# circuit2_ver2.net
KiCad netlist of a schematic drawn in Altium Designer
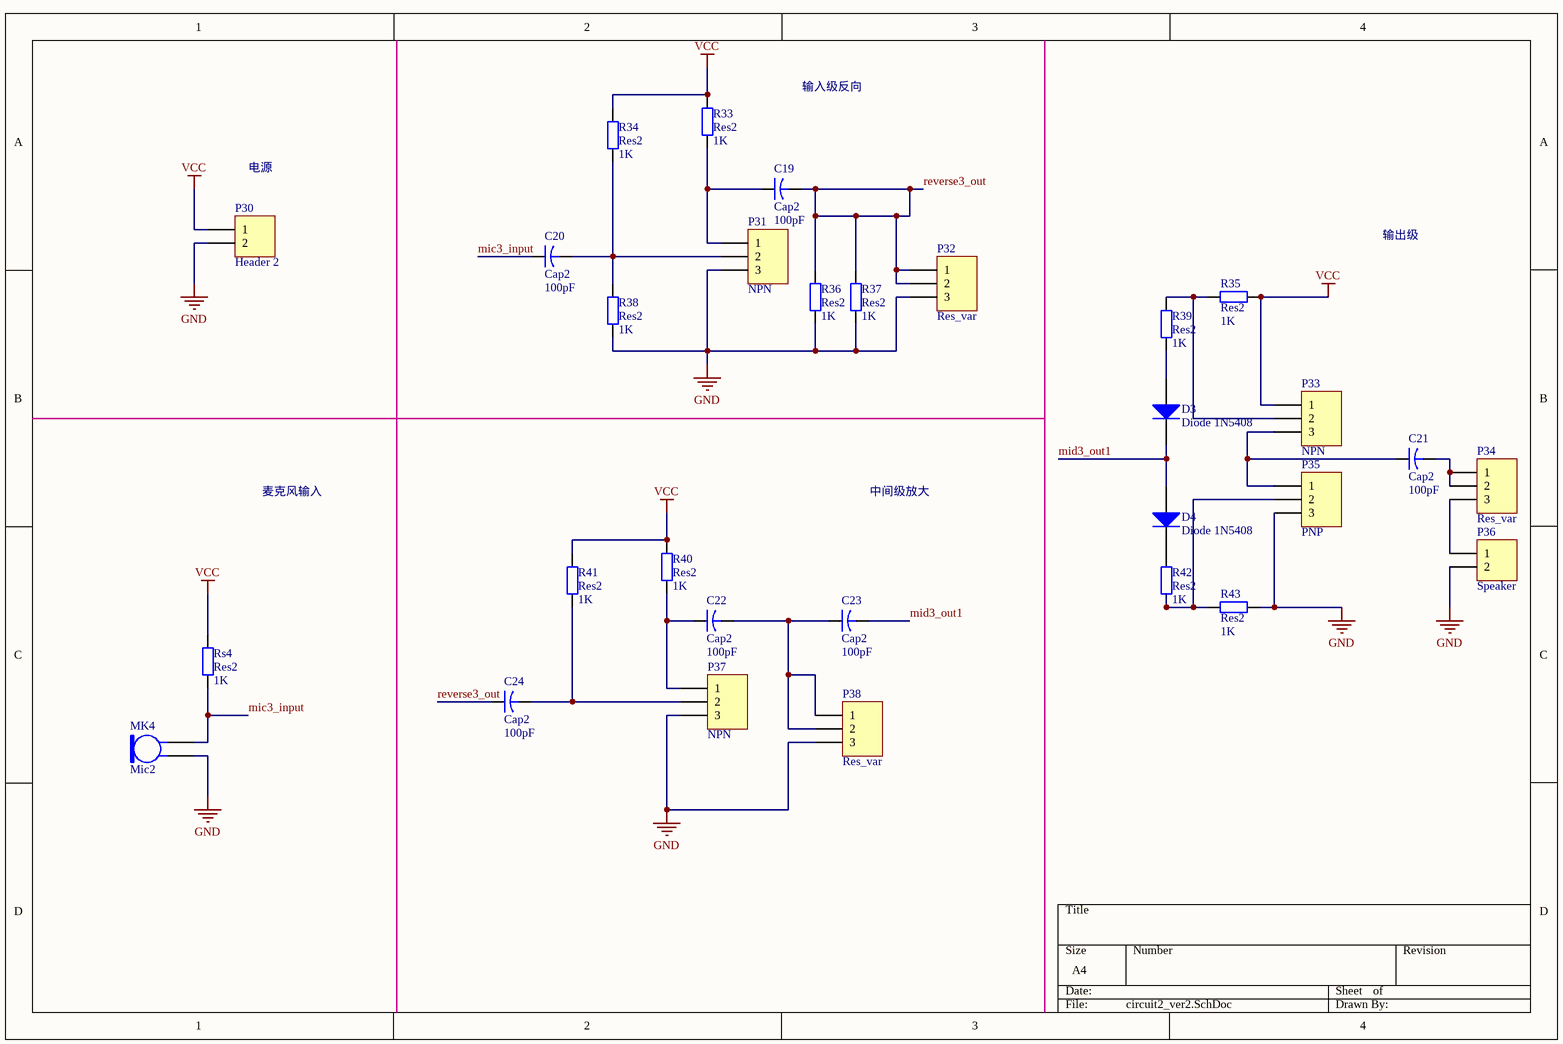
[diagram p0: circuit2_ver2.SchDoc]

(export (version "E")
  (design (tool "Eeschema 10.0.6"))
  (components
    (comp (ref "C19")
      (value "Cap2")
      (footprint "CAPR5-4X5")
      (description "Capacitor")
      (fields (field (name "ALTIUM_VALUE") "100pF") (field (name "PUBLISHER") "Altium Limited"))
      (libsource (lib "Miscellaneous Devices") (part "Cap2"))
    )
    (comp (ref "C20")
      (value "Cap2")
      (footprint "CAPR5-4X5")
      (description "Capacitor")
      (fields (field (name "ALTIUM_VALUE") "100pF") (field (name "PUBLISHER") "Altium Limited"))
      (libsource (lib "Miscellaneous Devices") (part "Cap2"))
    )
    (comp (ref "C21")
      (value "Cap2")
      (footprint "CAPR5-4X5")
      (description "Capacitor")
      (fields (field (name "ALTIUM_VALUE") "100pF") (field (name "PUBLISHER") "Altium Limited"))
      (libsource (lib "Miscellaneous Devices") (part "Cap2"))
    )
    (comp (ref "C22")
      (value "Cap2")
      (footprint "CAPR5-4X5")
      (description "Capacitor")
      (fields (field (name "ALTIUM_VALUE") "100pF") (field (name "PUBLISHER") "Altium Limited"))
      (libsource (lib "Miscellaneous Devices") (part "Cap2"))
    )
    (comp (ref "C23")
      (value "Cap2")
      (footprint "CAPR5-4X5")
      (description "Capacitor")
      (fields (field (name "ALTIUM_VALUE") "100pF") (field (name "PUBLISHER") "Altium Limited"))
      (libsource (lib "Miscellaneous Devices") (part "Cap2"))
    )
    (comp (ref "C24")
      (value "Cap2")
      (footprint "CAPR5-4X5")
      (description "Capacitor")
      (fields (field (name "ALTIUM_VALUE") "100pF") (field (name "PUBLISHER") "Altium Limited"))
      (libsource (lib "Miscellaneous Devices") (part "Cap2"))
    )
    (comp (ref "D3")
      (value "Diode 1N5408")
      (footprint "DO-201AD")
      (description "3 Amp Medium Power Silicon Rectifier Diode")
      (fields (field (name "PUBLISHER") "Altium Limited"))
      (libsource (lib "Miscellaneous Devices") (part "Diode 1N5408"))
    )
    (comp (ref "D4")
      (value "Diode 1N5408")
      (footprint "DO-201AD")
      (description "3 Amp Medium Power Silicon Rectifier Diode")
      (fields (field (name "PUBLISHER") "Altium Limited"))
      (libsource (lib "Miscellaneous Devices") (part "Diode 1N5408"))
    )
    (comp (ref "MK4")
      (value "Mic2")
      (footprint "PIN2")
      (description "Microphone")
      (fields (field (name "PUBLISHER") "Altium Limited"))
      (libsource (lib "Miscellaneous Devices") (part "Mic2"))
    )
    (comp (ref "P30")
      (value "Header 2")
      (footprint "HDR1X2")
      (description "Header, 2-Pin")
      (fields (field (name "PUBLISHER") "Altium Limited"))
      (libsource (lib "Miscellaneous Connectors") (part "Header 2"))
    )
    (comp (ref "P31")
      (value "NPN")
      (footprint "HDR1X3")
      (description "Header, 3-Pin")
      (fields (field (name "PUBLISHER") "Altium Limited"))
      (libsource (lib "Miscellaneous Connectors") (part "Header 3"))
    )
    (comp (ref "P32")
      (value "Res_var")
      (footprint "HDR1X3")
      (description "Header, 3-Pin")
      (fields (field (name "PUBLISHER") "Altium Limited"))
      (libsource (lib "Miscellaneous Connectors") (part "Header 3"))
    )
    (comp (ref "P33")
      (value "NPN")
      (footprint "HDR1X3")
      (description "Header, 3-Pin")
      (fields (field (name "PUBLISHER") "Altium Limited"))
      (libsource (lib "Miscellaneous Connectors") (part "Header 3"))
    )
    (comp (ref "P34")
      (value "Res_var")
      (footprint "HDR1X3")
      (description "Header, 3-Pin")
      (fields (field (name "PUBLISHER") "Altium Limited"))
      (libsource (lib "Miscellaneous Connectors") (part "Header 3"))
    )
    (comp (ref "P35")
      (value "PNP")
      (footprint "HDR1X3")
      (description "Header, 3-Pin")
      (fields (field (name "PUBLISHER") "Altium Limited"))
      (libsource (lib "Miscellaneous Connectors") (part "Header 3"))
    )
    (comp (ref "P36")
      (value "Speaker")
      (footprint "HDR1X2")
      (description "Header, 2-Pin")
      (fields (field (name "PUBLISHER") "Altium Limited"))
      (libsource (lib "Miscellaneous Connectors") (part "Header 2"))
    )
    (comp (ref "P37")
      (value "NPN")
      (footprint "HDR1X3")
      (description "Header, 3-Pin")
      (fields (field (name "PUBLISHER") "Altium Limited"))
      (libsource (lib "Miscellaneous Connectors") (part "Header 3"))
    )
    (comp (ref "P38")
      (value "Res_var")
      (footprint "HDR1X3")
      (description "Header, 3-Pin")
      (fields (field (name "PUBLISHER") "Altium Limited"))
      (libsource (lib "Miscellaneous Connectors") (part "Header 3"))
    )
    (comp (ref "R33")
      (value "Res2")
      (footprint "AXIAL-0.4")
      (description "Resistor")
      (fields (field (name "ALTIUM_VALUE") "1K") (field (name "PUBLISHER") "Altium Limited"))
      (libsource (lib "Miscellaneous Devices") (part "Res2"))
    )
    (comp (ref "R34")
      (value "Res2")
      (footprint "AXIAL-0.4")
      (description "Resistor")
      (fields (field (name "ALTIUM_VALUE") "1K") (field (name "PUBLISHER") "Altium Limited"))
      (libsource (lib "Miscellaneous Devices") (part "Res2"))
    )
    (comp (ref "R35")
      (value "Res2")
      (footprint "AXIAL-0.4")
      (description "Resistor")
      (fields (field (name "ALTIUM_VALUE") "1K") (field (name "PUBLISHER") "Altium Limited"))
      (libsource (lib "") (part "Res2_1"))
    )
    (comp (ref "R36")
      (value "Res2")
      (footprint "AXIAL-0.4")
      (description "Resistor")
      (fields (field (name "ALTIUM_VALUE") "1K") (field (name "PUBLISHER") "Altium Limited"))
      (libsource (lib "Miscellaneous Devices") (part "Res2"))
    )
    (comp (ref "R37")
      (value "Res2")
      (footprint "AXIAL-0.4")
      (description "Resistor")
      (fields (field (name "ALTIUM_VALUE") "1K") (field (name "PUBLISHER") "Altium Limited"))
      (libsource (lib "Miscellaneous Devices") (part "Res2"))
    )
    (comp (ref "R38")
      (value "Res2")
      (footprint "AXIAL-0.4")
      (description "Resistor")
      (fields (field (name "ALTIUM_VALUE") "1K") (field (name "PUBLISHER") "Altium Limited"))
      (libsource (lib "Miscellaneous Devices") (part "Res2"))
    )
    (comp (ref "R39")
      (value "Res2")
      (footprint "AXIAL-0.4")
      (description "Resistor")
      (fields (field (name "ALTIUM_VALUE") "1K") (field (name "PUBLISHER") "Altium Limited"))
      (libsource (lib "Miscellaneous Devices") (part "Res2"))
    )
    (comp (ref "R40")
      (value "Res2")
      (footprint "AXIAL-0.4")
      (description "Resistor")
      (fields (field (name "ALTIUM_VALUE") "1K") (field (name "PUBLISHER") "Altium Limited"))
      (libsource (lib "Miscellaneous Devices") (part "Res2"))
    )
    (comp (ref "R41")
      (value "Res2")
      (footprint "AXIAL-0.4")
      (description "Resistor")
      (fields (field (name "ALTIUM_VALUE") "1K") (field (name "PUBLISHER") "Altium Limited"))
      (libsource (lib "Miscellaneous Devices") (part "Res2"))
    )
    (comp (ref "R42")
      (value "Res2")
      (footprint "AXIAL-0.4")
      (description "Resistor")
      (fields (field (name "ALTIUM_VALUE") "1K") (field (name "PUBLISHER") "Altium Limited"))
      (libsource (lib "Miscellaneous Devices") (part "Res2"))
    )
    (comp (ref "R43")
      (value "Res2")
      (footprint "AXIAL-0.4")
      (description "Resistor")
      (fields (field (name "ALTIUM_VALUE") "1K") (field (name "PUBLISHER") "Altium Limited"))
      (libsource (lib "") (part "Res2_1"))
    )
    (comp (ref "Rs4")
      (value "Res2")
      (footprint "AXIAL-0.4")
      (description "Resistor")
      (fields (field (name "ALTIUM_VALUE") "1K") (field (name "PUBLISHER") "Altium Limited"))
      (libsource (lib "Miscellaneous Devices") (part "Res2"))
    )
  )
  (nets
    (net (code "1") (name "/mic3_input") (class "Default")
      (node (ref "C20") (pin "1") (pinfunction "1_1") (pintype "passive"))
      (node (ref "MK4") (pin "2") (pinfunction "2_2") (pintype "passive"))
      (node (ref "Rs4") (pin "1") (pinfunction "1_1") (pintype "passive"))
    )
    (net (code "2") (name "/mid3_out1") (class "Default")
      (node (ref "C23") (pin "2") (pinfunction "2_2") (pintype "passive"))
      (node (ref "D3") (pin "2") (pinfunction "K_2") (pintype "passive"))
      (node (ref "D4") (pin "1") (pinfunction "A_1") (pintype "passive"))
    )
    (net (code "3") (name "/reverse3_out") (class "Default")
      (node (ref "C19") (pin "2") (pinfunction "2_2") (pintype "passive"))
      (node (ref "C24") (pin "1") (pinfunction "1_1") (pintype "passive"))
      (node (ref "P32") (pin "1") (pinfunction "1_1") (pintype "passive"))
      (node (ref "P32") (pin "2") (pinfunction "2_2") (pintype "passive"))
      (node (ref "R36") (pin "2") (pinfunction "2_2") (pintype "passive"))
      (node (ref "R37") (pin "2") (pinfunction "2_2") (pintype "passive"))
    )
    (net (code "4") (name "GND") (class "Default")
      (node (ref "MK4") (pin "1") (pinfunction "1_1") (pintype "passive"))
      (node (ref "P30") (pin "2") (pinfunction "2_2") (pintype "passive"))
      (node (ref "P31") (pin "3") (pinfunction "3_3") (pintype "passive"))
      (node (ref "P32") (pin "3") (pinfunction "3_3") (pintype "passive"))
      (node (ref "P35") (pin "3") (pinfunction "3_3") (pintype "passive"))
      (node (ref "P36") (pin "2") (pinfunction "2_2") (pintype "passive"))
      (node (ref "P37") (pin "3") (pinfunction "3_3") (pintype "passive"))
      (node (ref "P38") (pin "3") (pinfunction "3_3") (pintype "passive"))
      (node (ref "R36") (pin "1") (pinfunction "1_1") (pintype "passive"))
      (node (ref "R37") (pin "1") (pinfunction "1_1") (pintype "passive"))
      (node (ref "R38") (pin "1") (pinfunction "1_1") (pintype "passive"))
      (node (ref "R43") (pin "1") (pinfunction "1_1") (pintype "passive"))
    )
    (net (code "5") (name "Net-(C19-Pad1)") (class "Default")
      (node (ref "C19") (pin "1") (pinfunction "1_1") (pintype "passive"))
      (node (ref "P31") (pin "1") (pinfunction "1_1") (pintype "passive"))
      (node (ref "R33") (pin "1") (pinfunction "1_1") (pintype "passive"))
    )
    (net (code "6") (name "Net-(C20-Pad2)") (class "Default")
      (node (ref "C20") (pin "2") (pinfunction "2_2") (pintype "passive"))
      (node (ref "P31") (pin "2") (pinfunction "2_2") (pintype "passive"))
      (node (ref "R34") (pin "1") (pinfunction "1_1") (pintype "passive"))
      (node (ref "R38") (pin "2") (pinfunction "2_2") (pintype "passive"))
    )
    (net (code "7") (name "Net-(C21-Pad1)") (class "Default")
      (node (ref "C21") (pin "1") (pinfunction "1_1") (pintype "passive"))
      (node (ref "P33") (pin "3") (pinfunction "3_3") (pintype "passive"))
      (node (ref "P35") (pin "1") (pinfunction "1_1") (pintype "passive"))
    )
    (net (code "8") (name "Net-(C21-Pad2)") (class "Default")
      (node (ref "C21") (pin "2") (pinfunction "2_2") (pintype "passive"))
      (node (ref "P34") (pin "1") (pinfunction "1_1") (pintype "passive"))
      (node (ref "P34") (pin "2") (pinfunction "2_2") (pintype "passive"))
    )
    (net (code "9") (name "Net-(C22-Pad1)") (class "Default")
      (node (ref "C22") (pin "1") (pinfunction "1_1") (pintype "passive"))
      (node (ref "P37") (pin "1") (pinfunction "1_1") (pintype "passive"))
      (node (ref "R40") (pin "1") (pinfunction "1_1") (pintype "passive"))
    )
    (net (code "10") (name "Net-(C22-Pad2)") (class "Default")
      (node (ref "C22") (pin "2") (pinfunction "2_2") (pintype "passive"))
      (node (ref "C23") (pin "1") (pinfunction "1_1") (pintype "passive"))
      (node (ref "P38") (pin "1") (pinfunction "1_1") (pintype "passive"))
      (node (ref "P38") (pin "2") (pinfunction "2_2") (pintype "passive"))
    )
    (net (code "11") (name "Net-(C24-Pad2)") (class "Default")
      (node (ref "C24") (pin "2") (pinfunction "2_2") (pintype "passive"))
      (node (ref "P37") (pin "2") (pinfunction "2_2") (pintype "passive"))
      (node (ref "R41") (pin "1") (pinfunction "1_1") (pintype "passive"))
    )
    (net (code "12") (name "Net-(D3-A)") (class "Default")
      (node (ref "D3") (pin "1") (pinfunction "A_1") (pintype "passive"))
      (node (ref "R39") (pin "1") (pinfunction "1_1") (pintype "passive"))
    )
    (net (code "13") (name "Net-(D4-K)") (class "Default")
      (node (ref "D4") (pin "2") (pinfunction "K_2") (pintype "passive"))
      (node (ref "R42") (pin "2") (pinfunction "2_2") (pintype "passive"))
    )
    (net (code "14") (name "Net-(P33-Pad2)") (class "Default")
      (node (ref "P33") (pin "2") (pinfunction "2_2") (pintype "passive"))
      (node (ref "R35") (pin "2") (pinfunction "2_2") (pintype "passive"))
      (node (ref "R39") (pin "2") (pinfunction "2_2") (pintype "passive"))
    )
    (net (code "15") (name "Net-(P34-Pad3)") (class "Default")
      (node (ref "P34") (pin "3") (pinfunction "3_3") (pintype "passive"))
      (node (ref "P36") (pin "1") (pinfunction "1_1") (pintype "passive"))
    )
    (net (code "16") (name "Net-(P35-Pad2)") (class "Default")
      (node (ref "P35") (pin "2") (pinfunction "2_2") (pintype "passive"))
      (node (ref "R42") (pin "1") (pinfunction "1_1") (pintype "passive"))
      (node (ref "R43") (pin "2") (pinfunction "2_2") (pintype "passive"))
    )
    (net (code "17") (name "VCC") (class "Default")
      (node (ref "P30") (pin "1") (pinfunction "1_1") (pintype "passive"))
      (node (ref "P33") (pin "1") (pinfunction "1_1") (pintype "passive"))
      (node (ref "R33") (pin "2") (pinfunction "2_2") (pintype "passive"))
      (node (ref "R34") (pin "2") (pinfunction "2_2") (pintype "passive"))
      (node (ref "R35") (pin "1") (pinfunction "1_1") (pintype "passive"))
      (node (ref "R40") (pin "2") (pinfunction "2_2") (pintype "passive"))
      (node (ref "R41") (pin "2") (pinfunction "2_2") (pintype "passive"))
      (node (ref "Rs4") (pin "2") (pinfunction "2_2") (pintype "passive"))
    )
  )
)
